# StepDown_LM2596.net
KiCad netlist of a schematic drawn in Altium Designer
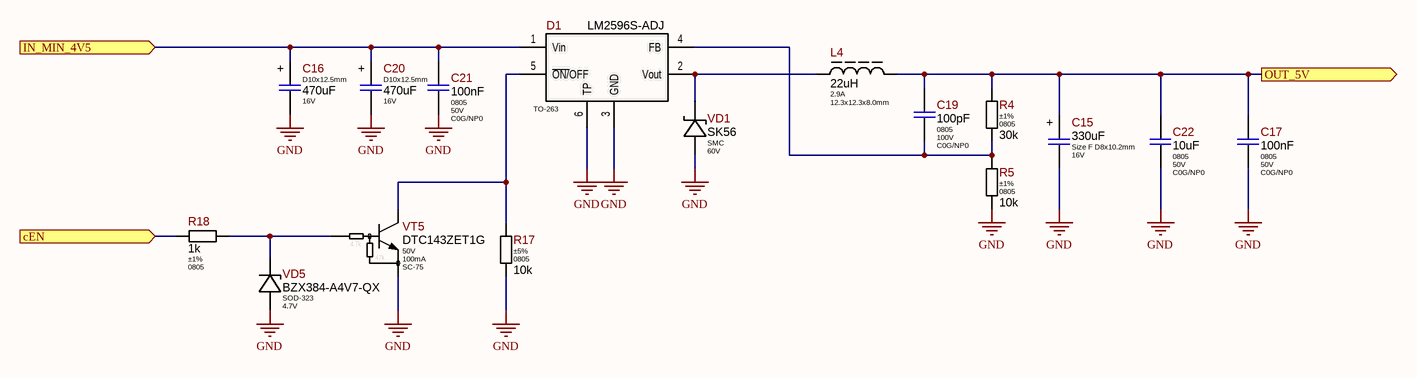
[diagram p0: StepDown_LM2596.SchDoc]

(export (version "E")
  (design (tool "Eeschema 10.0.6"))
  (components
    (comp (ref "C15")
      (value "330uF")
      (footprint "CAP-AE-830x1020H30_MED")
      (fields
        (field (name "PACKAGE") "Size F D8x10.2mm")
        (field (name "VOLTAGE") "16V")
        (field (name "PART NUMBER") "EEEFK1C331P")
        (field (name "MANUFACTURER") "Panasonic")
        (field (name "TOLERANCE") "±20%")
      )
      (libsource (lib "vitech_capacitors") (part "EEE-1HA330AP"))
    )
    (comp (ref "C16")
      (value "470uF")
      (footprint "CAP-AE-PTH-100D10x125H15")
      (description "470uF 16V D10x12.5mm Electrolytic Low Impedance")
      (fields
        (field (name "PACKAGE") "D10x12.5mm")
        (field (name "VOLTAGE") "16V")
        (field (name "PART NUMBER") "EXR471M16B")
        (field (name "MANUFACTURER") "Hitano")
      )
      (libsource (lib "capacitors") (part "EXR471M16B"))
    )
    (comp (ref "C17")
      (value "100nF")
      (footprint "C_CERAMIC_0805_HI")
      (fields
        (field (name "PART NUMBER") "**")
        (field (name "MANUFACTURER") "Hitano")
        (field (name "TOLERANCE") "±5%")
        (field (name "PACKAGE") "0805")
        (field (name "VOLTAGE") "50V")
        (field (name "DIELECTRIC TYPE") "C0G/NP0")
      )
      (libsource (lib "vitech_capacitors") (part "CERAMIC_0805"))
    )
    (comp (ref "C19")
      (value "100pF")
      (footprint "CAP-0805(2012)X60T10")
      (description "100pF 100V C0G, NP0 ±5% 0805 Ceramic Capacitor RoHS")
      (fields
        (field (name "PACKAGE") "0805")
        (field (name "VOLTAGE") "100V")
        (field (name "DIELECTRIC TYPE") "C0G/NP0")
        (field (name "PART NUMBER") "CC0805JRNPO0BN101")
        (field (name "MANUFACTURER") "Yageo")
      )
      (libsource (lib "capacitors") (part "CC0805JRNPO0BN101"))
    )
    (comp (ref "C20")
      (value "470uF")
      (footprint "CAP-AE-PTH-100D10x125H15")
      (description "470uF 16V D10x12.5mm Electrolytic Low Impedance")
      (fields
        (field (name "PACKAGE") "D10x12.5mm")
        (field (name "VOLTAGE") "16V")
        (field (name "PART NUMBER") "ECAP 470/16V 0812 105'C EHR")
        (field (name "MANUFACTURER") "Hitano")
      )
      (libsource (lib "capacitors") (part "EXR471M16B"))
    )
    (comp (ref "C21")
      (value "100nF")
      (footprint "C_CERAMIC_0805_HI")
      (fields
        (field (name "PART NUMBER") "**")
        (field (name "MANUFACTURER") "Hitano")
        (field (name "TOLERANCE") "±5%")
        (field (name "PACKAGE") "0805")
        (field (name "VOLTAGE") "50V")
        (field (name "DIELECTRIC TYPE") "C0G/NP0")
      )
      (libsource (lib "vitech_capacitors") (part "CERAMIC_0805"))
    )
    (comp (ref "C22")
      (value "10uF")
      (footprint "C_CERAMIC_0805_HI")
      (fields
        (field (name "PART NUMBER") "**")
        (field (name "MANUFACTURER") "Hitano")
        (field (name "TOLERANCE") "±5%")
        (field (name "PACKAGE") "0805")
        (field (name "VOLTAGE") "50V")
        (field (name "DIELECTRIC TYPE") "C0G/NP0")
      )
      (libsource (lib "vitech_capacitors") (part "CERAMIC_0805"))
    )
    (comp (ref "D1")
      (value "LM2596S-ADJ")
      (footprint "TO-263-5-1")
      (description "SIMPLE SWITCHER Power Converter 150-kHz 3-A Step-Down Voltage Regulator")
      (fields
        (field (name "PACKAGE") "TO-263")
        (field (name "PART NUMBER") "LM2596S-ADJ")
        (field (name "MANUFACTURER") "Texas Instruments")
      )
      (libsource (lib "ic") (part "LM2596S-ADJ"))
    )
    (comp (ref "L4")
      (value "22uH")
      (footprint "CDRH127-Series")
      (description "22 µH Shielded Inductor 2.9 A 66mOhm Max Nonstandard")
      (fields
        (field (name "CURRENT") "2.9A")
        (field (name "PACKAGE") "12.3x12.3x8.0mm")
        (field (name "PART NUMBER") "CDRH124NP-220MC")
        (field (name "TOLERANCE") "±20%")
      )
      (libsource (lib "vitech_inductors") (part "CDRH127NP-102MC"))
    )
    (comp (ref "R4")
      (value "30k")
      (footprint "R_ANY_CHIP_0805_MED")
      (description "30 kOhms ±1%, 1/8W 0805 Thick Film Resistor")
      (fields
        (field (name "TOLERANCE") "±1%")
        (field (name "PACKAGE") "0805")
        (field (name "PART NUMBER") "RC0805FR-0730KL")
        (field (name "MANUFACTURER") "Yageo")
      )
      (libsource (lib "resistors") (part "RC0805FR-0730KL"))
    )
    (comp (ref "R5")
      (value "10k")
      (footprint "R_ANY_CHIP_0805_MED")
      (description "10 kOhms ±1%, 1/8W 0805 Thick Film Resistor")
      (fields
        (field (name "TOLERANCE") "±1%")
        (field (name "PACKAGE") "0805")
        (field (name "PART NUMBER") "RC0805FR-0710K2L")
        (field (name "MANUFACTURER") "Yageo")
      )
      (libsource (lib "resistors") (part "RC0805FR-0710K2L"))
    )
    (comp (ref "R17")
      (value "10k")
      (footprint "R_ANY_CHIP_0805_MED")
      (description "2.2 kOhms ±5% 1/8W 0805 Thick Film Resistor")
      (fields
        (field (name "TOLERANCE") "±5%")
        (field (name "PACKAGE") "0805")
        (field (name "PART NUMBER") "RC0805JR-072K2L")
        (field (name "MANUFACTURER") "Yageo")
      )
      (libsource (lib "resistors") (part "RC0805JR-072K2L"))
    )
    (comp (ref "R18")
      (value "1k")
      (footprint "R_ANY_CHIP_0805_MED")
      (description "2.2 kOhms ±1% 1/8W 0805 Thick Film Resistor")
      (fields
        (field (name "TOLERANCE") "±1%")
        (field (name "PACKAGE") "0805")
        (field (name "PART NUMBER") "RC0805FR-072K2L")
        (field (name "MANUFACTURER") "Yageo")
      )
      (libsource (lib "resistors") (part "RC0805FR-072K2L"))
    )
    (comp (ref "VD1")
      (value "SK56")
      (footprint "SMC")
      (description "Diode Schottky 60V 5A, SMC")
      (fields
        (field (name "PART NUMBER") "SK56")
        (field (name "PACKAGE") "SMC")
        (field (name "VOLTAGE") "60V")
        (field (name "MANUFACTURER") "KLS")
      )
      (libsource (lib "vitech_semiconductors") (part "SS34"))
    )
    (comp (ref "VD5")
      (value "BZX384-A4V7-QX")
      (footprint "SOD-323_MED")
      (description "Zener Diode 4.7V, 300mW, ±1%, Leakage 3uA @ 2V, SOD-323")
      (fields
        (field (name "PART NUMBER") "BZX384-A4V7-QX")
        (field (name "PACKAGE") "SOD-323")
        (field (name "VOLTAGE") "4.7V")
        (field (name "MANUFACTURER") "Nexperia USA")
      )
      (libsource (lib "vitech_semiconductors") (part "BZX384-A4V7-QX"))
    )
    (comp (ref "VT5")
      (value "DTC143ZET1G")
      (footprint "SOT-416")
      (description "50V, 100mA Low Vce(sat) NPN Digital Transistor, Pre-Biased 4.7k/47k (with built-in resistors)")
      (fields
        (field (name "PART NUMBER") "DTC143ZET1G")
        (field (name "VCE") "50V")
        (field (name "IC") "100mA")
        (field (name "PACKAGE") "SC-75")
        (field (name "MANUFACTURER") "Onsemi")
      )
      (libsource (lib "vitech_semiconductors") (part "DTC143ZET1G"))
    )
  )
  (nets
    (net (code "1") (name "/IN_MIN_4V5") (class "Default")
      (node (ref "C16") (pin "1") (pinfunction "1_1") (pintype "passive"))
      (node (ref "C20") (pin "1") (pinfunction "1_1") (pintype "passive"))
      (node (ref "C21") (pin "1") (pinfunction "1_1") (pintype "passive"))
      (node (ref "D1") (pin "1") (pinfunction "Vin_1") (pintype "passive"))
    )
    (net (code "2") (name "/OUT_5V") (class "Default")
      (node (ref "C15") (pin "1") (pinfunction "1_1") (pintype "passive"))
      (node (ref "C17") (pin "1") (pinfunction "1_1") (pintype "passive"))
      (node (ref "C19") (pin "2") (pinfunction "2_2") (pintype "passive"))
      (node (ref "C22") (pin "1") (pinfunction "1_1") (pintype "passive"))
      (node (ref "L4") (pin "2") (pintype "passive"))
      (node (ref "R4") (pin "1") (pintype "passive"))
    )
    (net (code "3") (name "/cEN") (class "Default") (node (ref "R18") (pin "1") (pintype "passive")))
    (net (code "4") (name "GND") (class "Default")
      (node (ref "C15") (pin "2") (pinfunction "2_2") (pintype "passive"))
      (node (ref "C16") (pin "2") (pinfunction "2_2") (pintype "passive"))
      (node (ref "C17") (pin "2") (pinfunction "2_2") (pintype "passive"))
      (node (ref "C20") (pin "2") (pinfunction "2_2") (pintype "passive"))
      (node (ref "C21") (pin "2") (pinfunction "2_2") (pintype "passive"))
      (node (ref "C22") (pin "2") (pinfunction "2_2") (pintype "passive"))
      (node (ref "D1") (pin "3") (pinfunction "GND_3") (pintype "passive"))
      (node (ref "D1") (pin "6") (pinfunction "TP_6") (pintype "passive"))
      (node (ref "R17") (pin "2") (pintype "passive"))
      (node (ref "R5") (pin "2") (pintype "passive"))
      (node (ref "VD1") (pin "AN") (pintype "passive"))
      (node (ref "VD5") (pin "AN") (pintype "passive"))
      (node (ref "VT5") (pin "2") (pinfunction "E_2") (pintype "passive"))
    )
    (net (code "5") (name "Net-(D1-FB)") (class "Default")
      (node (ref "C19") (pin "1") (pinfunction "1_1") (pintype "passive"))
      (node (ref "D1") (pin "4") (pinfunction "FB_4") (pintype "passive"))
      (node (ref "R4") (pin "2") (pintype "passive"))
      (node (ref "R5") (pin "1") (pintype "passive"))
    )
    (net (code "6") (name "Net-(D1-Vout)") (class "Default")
      (node (ref "D1") (pin "2") (pinfunction "Vout_2") (pintype "passive"))
      (node (ref "L4") (pin "1") (pintype "passive"))
      (node (ref "VD1") (pin "CA") (pintype "passive"))
    )
    (net (code "7") (name "Net-(D1-~{ON{slash}}OFF)") (class "Default")
      (node (ref "D1") (pin "5") (pinfunction "~{ON/}OFF_5") (pintype "passive"))
      (node (ref "R17") (pin "1") (pintype "passive"))
      (node (ref "VT5") (pin "3") (pinfunction "C_3") (pintype "passive"))
    )
    (net (code "8") (name "Net-(VT5-B)") (class "Default")
      (node (ref "R18") (pin "2") (pintype "passive"))
      (node (ref "VD5") (pin "CA") (pintype "passive"))
      (node (ref "VT5") (pin "1") (pinfunction "B_1") (pintype "passive"))
    )
  )
)
